# Voltage_Regulator.net
KiCad netlist of a schematic drawn in Altium Designer
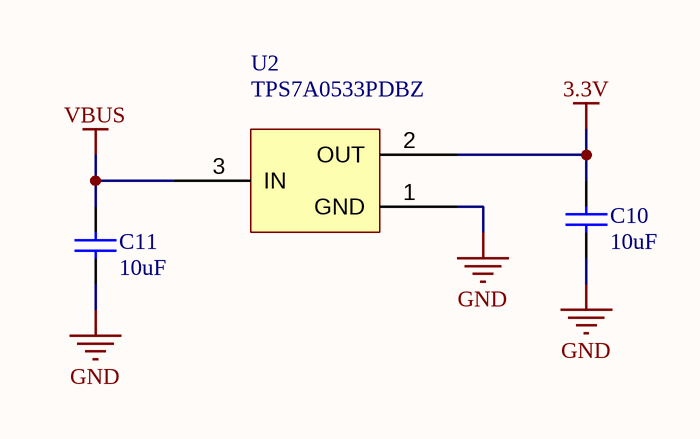
[diagram p0: Voltage Regulator.SchDoc]

(export (version "E")
  (design (tool "Eeschema 10.0.6"))
  (components
    (comp (ref "C10") (value "10uF") (footprint "Capacitor 0402") (libsource (lib "x-io") (part "Capacitor")))
    (comp (ref "C11") (value "10uF") (footprint "Capacitor 0402") (libsource (lib "x-io") (part "Capacitor")))
    (comp (ref "U2")
      (value "TPS7A0533PDBZ")
      (footprint "SOT-23")
      (libsource (lib "x-io") (part "TPS7A0533PDBZ"))
    )
  )
  (nets
    (net (code "1") (name "3.3V") (class "Default")
      (node (ref "C10") (pin "2") (pinfunction "2_2") (pintype "passive"))
      (node (ref "U2") (pin "2") (pinfunction "OUT_2") (pintype "passive"))
    )
    (net (code "2") (name "GND") (class "Default")
      (node (ref "C10") (pin "1") (pinfunction "1_1") (pintype "passive"))
      (node (ref "C11") (pin "1") (pinfunction "1_1") (pintype "passive"))
      (node (ref "U2") (pin "1") (pinfunction "GND_1") (pintype "passive"))
    )
    (net (code "3") (name "VBUS") (class "Default")
      (node (ref "C11") (pin "2") (pinfunction "2_2") (pintype "passive"))
      (node (ref "U2") (pin "3") (pinfunction "IN_3") (pintype "passive"))
    )
  )
)
